# Smartfin_Main_PCBA_Control.net
KiCad netlist of a schematic drawn in Altium Designer
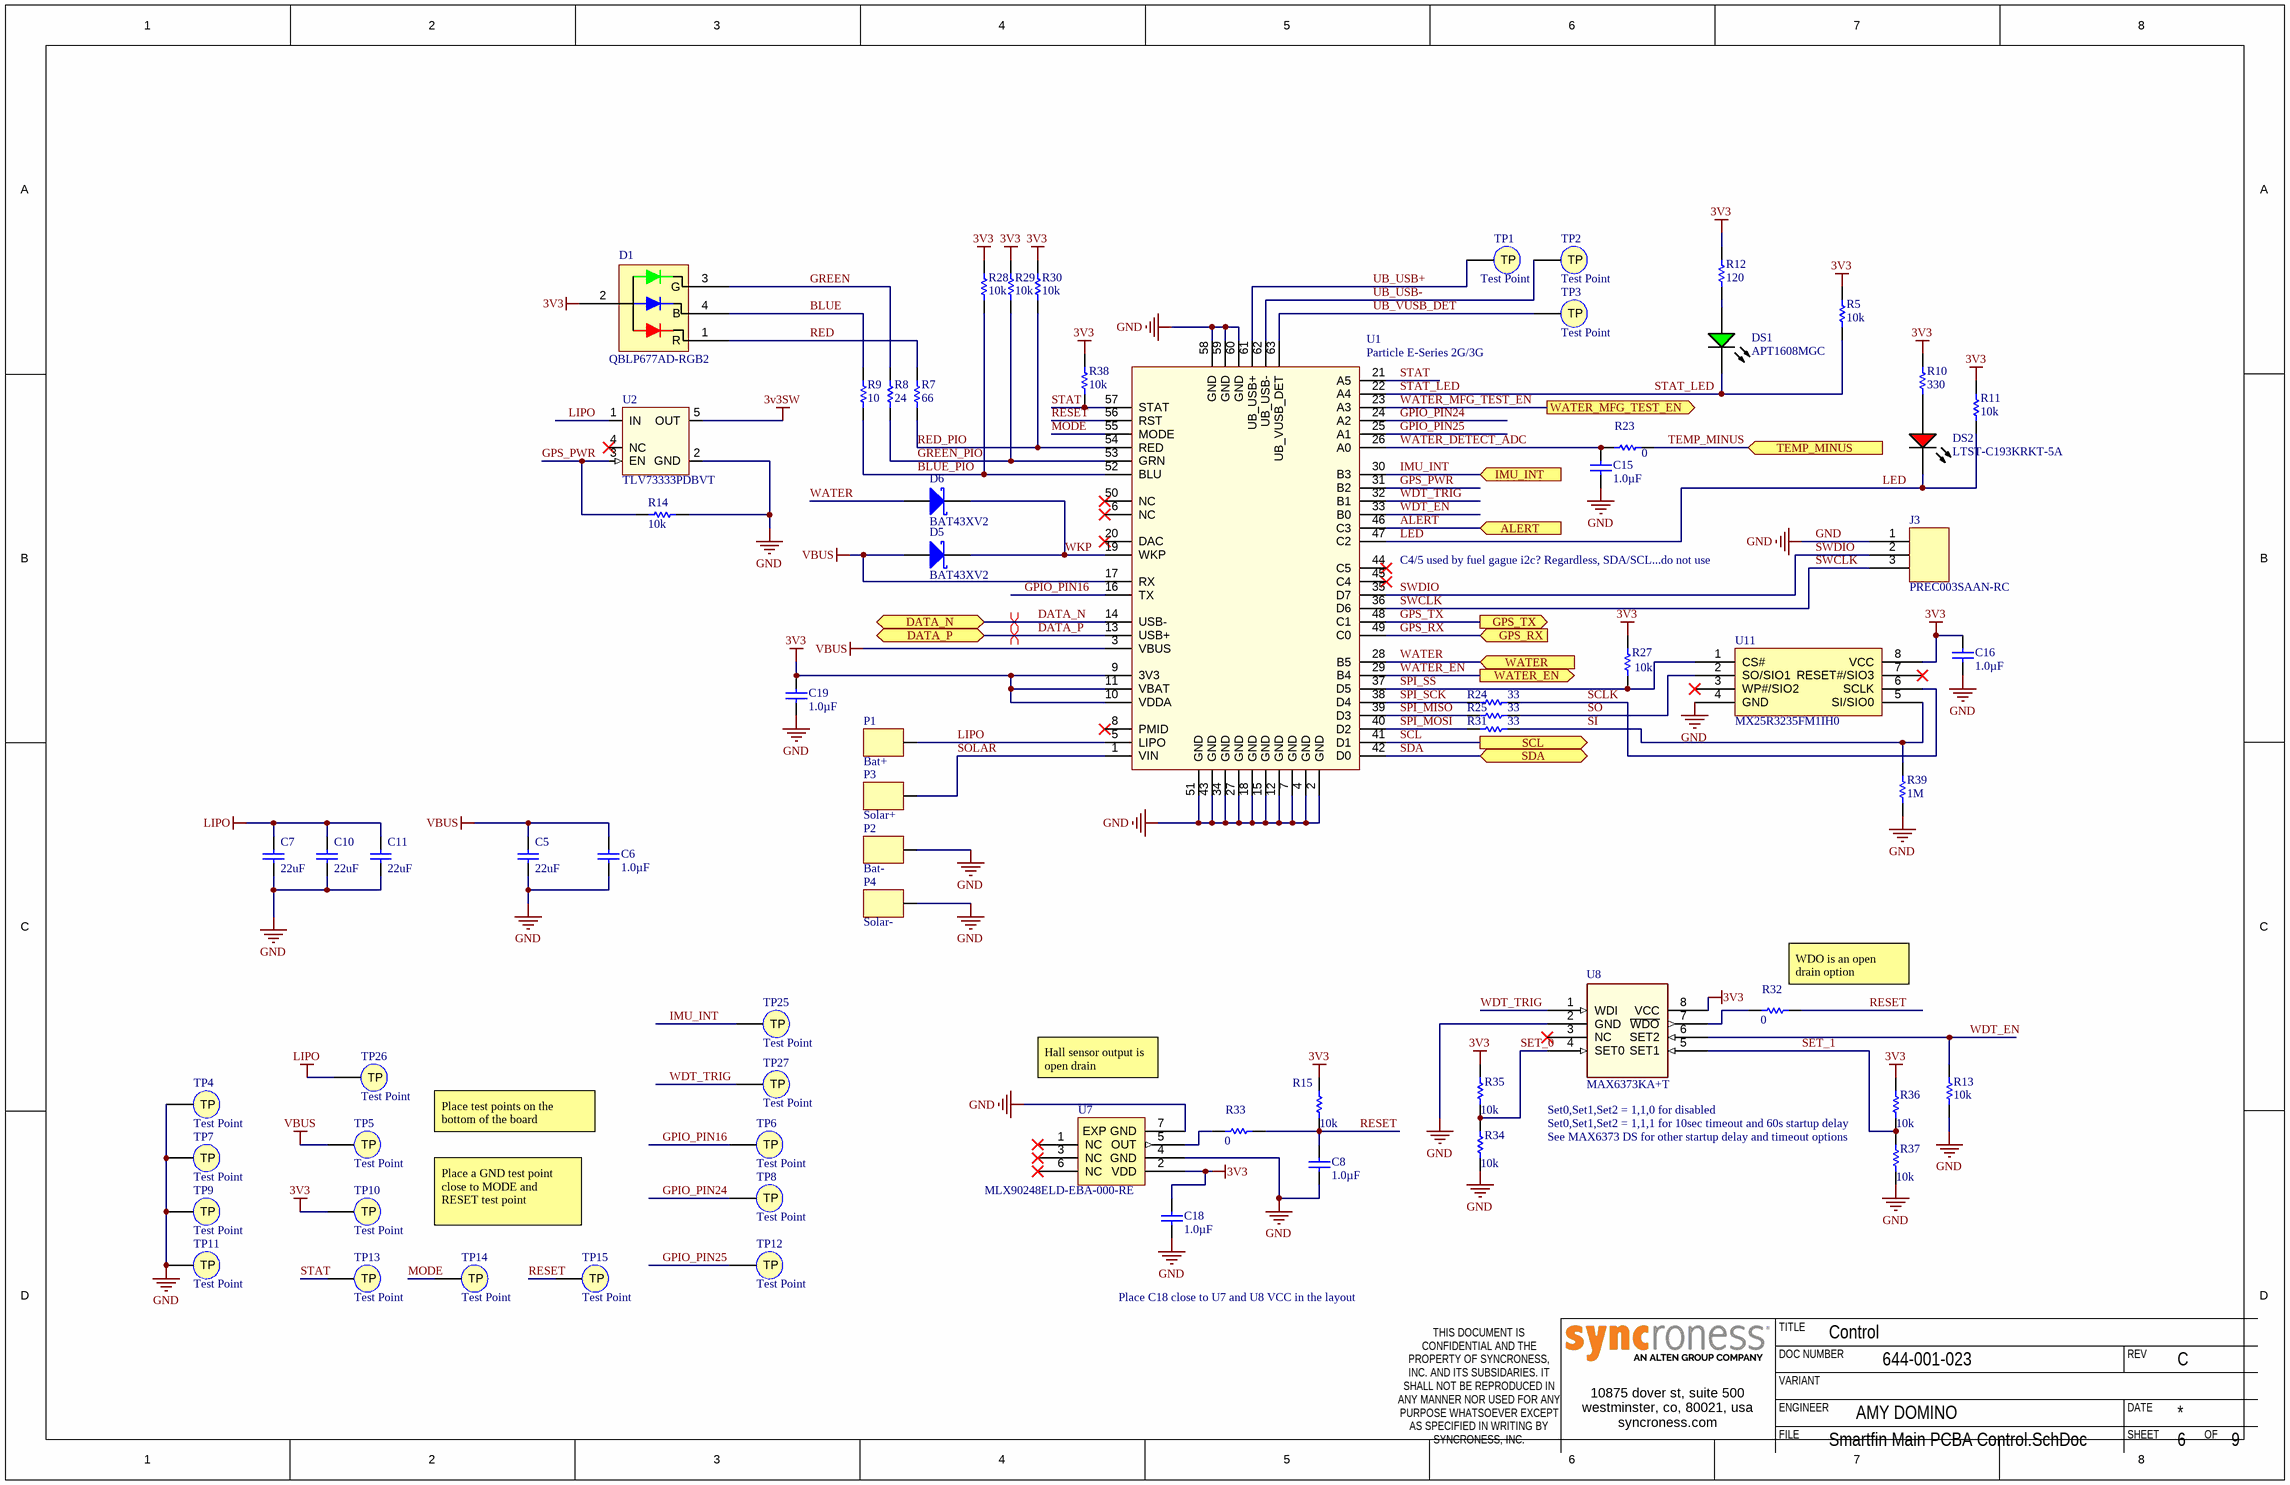
[diagram p0: Smartfin Main PCBA Control.SchDoc]

(export (version "E")
  (design (tool "Eeschema 10.0.6"))
  (components
    (comp (ref "C5")
      (value "22uF")
      (footprint "CAPC0603(1608)100_N")
      (description "CAP CER 22UF 10V X5R 0603")
      (fields (field (name "TOLERANCE") "20%") (field (name "MANUFACTURER") "Murata Electronics"))
      (libsource (lib "Syncroness Vault") (part "CAP"))
    )
    (comp (ref "C6")
      (value "1.0µF")
      (footprint "CAPC0402(1005)60_N")
      (description "CAP CER 1UF 10V 10% X5R 0402")
      (fields
        (field (name "MANUFACTURER") "Yageo")
        (field (name "MANUFACTURER PART NUMBER") "CC0402KRX5R6BB105")
      )
      (libsource (lib "Syncroness Vault") (part "CAP"))
    )
    (comp (ref "C7")
      (value "22uF")
      (footprint "CAPC0603(1608)100_N")
      (description "CAP CER 22UF 10V X5R 0603")
      (fields (field (name "TOLERANCE") "20%") (field (name "MANUFACTURER") "Murata Electronics"))
      (libsource (lib "Syncroness Vault") (part "CAP"))
    )
    (comp (ref "C8")
      (value "1.0µF")
      (footprint "CAPC0402(1005)60_N")
      (description "CAP CER 1UF 10V 10% X5R 0402")
      (fields
        (field (name "MANUFACTURER") "Yageo")
        (field (name "MANUFACTURER PART NUMBER") "CC0402KRX5R6BB105")
      )
      (libsource (lib "Syncroness Vault") (part "CAP"))
    )
    (comp (ref "C10")
      (value "22uF")
      (footprint "CAPC0603(1608)100_N")
      (description "CAP CER 22UF 10V X5R 0603")
      (fields (field (name "TOLERANCE") "20%") (field (name "MANUFACTURER") "Murata Electronics"))
      (libsource (lib "Syncroness Vault") (part "CAP"))
    )
    (comp (ref "C11")
      (value "22uF")
      (footprint "CAPC0603(1608)100_N")
      (description "CAP CER 22UF 10V X5R 0603")
      (fields (field (name "TOLERANCE") "20%") (field (name "MANUFACTURER") "Murata Electronics"))
      (libsource (lib "Syncroness Vault") (part "CAP"))
    )
    (comp (ref "C15")
      (value "1.0µF")
      (footprint "CAPC0402(1005)60_N")
      (description "CAP CER 1UF 10V 10% X5R 0402")
      (fields
        (field (name "MANUFACTURER") "Yageo")
        (field (name "MANUFACTURER PART NUMBER") "CC0402KRX5R6BB105")
      )
      (libsource (lib "Syncroness Vault") (part "CAP"))
    )
    (comp (ref "C16")
      (value "1.0µF")
      (footprint "CAPC0402(1005)60_N")
      (description "CAP CER 1UF 10V 10% X5R 0402")
      (fields
        (field (name "MANUFACTURER") "Yageo")
        (field (name "MANUFACTURER PART NUMBER") "CC0402KRX5R6BB105")
      )
      (libsource (lib "Syncroness Vault") (part "CAP"))
    )
    (comp (ref "C18")
      (value "1.0µF")
      (footprint "CAPC0402(1005)60_N")
      (description "CAP CER 1UF 10V 10% X5R 0402")
      (fields
        (field (name "MANUFACTURER") "Yageo")
        (field (name "MANUFACTURER PART NUMBER") "CC0402KRX5R6BB105")
      )
      (libsource (lib "Syncroness Vault") (part "CAP"))
    )
    (comp (ref "C19")
      (value "1.0µF")
      (footprint "CAPC0402(1005)60_N")
      (description "CAP CER 1UF 10V 10% X5R 0402")
      (fields
        (field (name "MANUFACTURER") "Yageo")
        (field (name "MANUFACTURER PART NUMBER") "CC0402KRX5R6BB105")
      )
      (libsource (lib "Syncroness Vault") (part "CAP"))
    )
    (comp (ref "D1")
      (value "QBLP677AD-RGB2")
      (footprint "QBLP677AD-RGB2-Footprint-1")
      (description "LED RGB, 3528 PLCC4 DOME LENS, 2")
      (fields (field (name "MANUFACTURER") "QT Brightek (QTB)"))
      (libsource (lib "Syncroness Vault") (part "QBLP677-RGB(HIGHBRIGHT)"))
    )
    (comp (ref "D5")
      (value "BAT43XV2")
      (footprint "SOD-523F")
      (description "DIODE SCHOTTKY 30V 200MA SOD523F")
      (fields (field (name "MANUFACTURER") "ON Semiconductor"))
      (libsource (lib "Syncroness Vault") (part "Schottky Diode"))
    )
    (comp (ref "D6")
      (value "BAT43XV2")
      (footprint "SOD-523F")
      (description "DIODE SCHOTTKY 30V 200MA SOD523F")
      (fields (field (name "MANUFACTURER") "ON Semiconductor"))
      (libsource (lib "Syncroness Vault") (part "Schottky Diode"))
    )
    (comp (ref "DS1")
      (value "APT1608MGC")
      (footprint "LED1608X08N")
      (description "LED 1.6X0.8MM 570NM GRN CLR SMD")
      (fields (field (name "MANUFACTURER") "Kingbright"))
      (libsource (lib "Syncroness Vault") (part "Green LED"))
    )
    (comp (ref "DS2")
      (value "LTST-C193KRKT-5A")
      (footprint "LTST-C193KRKT-5A_V")
      (description "LED RED CLEAR CHIP SMD 0603")
      (fields (field (name "MANUFACTURER") "Lite-On Inc."))
      (libsource (lib "Syncroness Vault") (part "LED-RED-AK-2"))
    )
    (comp (ref "J3")
      (value "PREC003SAAN-RC")
      (footprint "HDR_Single_100mil_3D_3")
      (description "CONN HEADER .100\" SNGL STR 3POS")
      (fields (field (name "MANUFACTURER") "Sullins Connector Solutions"))
      (libsource (lib "Syncroness Vault") (part "PREC003SAAN-RC"))
    )
    (comp (ref "P1")
      (value "Bat+")
      (footprint "Battery Pad-Footprint-1")
      (description "Battery Pad for Smartfin Main board")
      (libsource (lib "Syncroness Vault") (part "Battery Pad"))
    )
    (comp (ref "P2")
      (value "Bat-")
      (footprint "Battery Pad-Footprint-1")
      (description "Battery Pad for Smartfin Main board")
      (libsource (lib "Syncroness Vault") (part "Battery Pad"))
    )
    (comp (ref "P3")
      (value "Solar+")
      (footprint "Battery Pad-Footprint-1")
      (description "Battery Pad for Smartfin Main board")
      (libsource (lib "Syncroness Vault") (part "Battery Pad"))
    )
    (comp (ref "P4")
      (value "Solar-")
      (footprint "Battery Pad-Footprint-1")
      (description "Battery Pad for Smartfin Main board")
      (libsource (lib "Syncroness Vault") (part "Battery Pad"))
    )
    (comp (ref "R5")
      (value "10k")
      (footprint "RESC0402(1005)_N")
      (description "RES SMD 10K OHM 0.1% 1/16W 0402")
      (fields
        (field (name "TOLERANCE") "±0.1%")
        (field (name "MANUFACTURER") "Panasonic Electronic Components")
      )
      (libsource (lib "Syncroness Vault") (part "RES"))
    )
    (comp (ref "R7")
      (value "66")
      (footprint "RESC1005X40X25LL05T10")
      (description "Res Thick Film 0402 66.5 Ohm 1% 1/16W ±100ppm/°C Molded SMD Paper T/R")
      (fields (field (name "PART NUMBER") "RC0402FR-0766R5L") (field (name "MANUFACTURER") "Yageo"))
      (libsource (lib "Altium Content Vault") (part "RES"))
    )
    (comp (ref "R8")
      (value "24")
      (footprint "RESC1005X40X25ML10T10")
      (fields
        (field (name "MANUFACTURER") "TE Connectivity / AMP")
        (field (name "PART NUMBER") "CRG0402F24R")
        (field (name "TOLERANCE") "1%")
      )
      (libsource (lib "Altium Content Vault") (part "RES"))
    )
    (comp (ref "R9")
      (value "10")
      (footprint "RESC1005X40X25ML05T10")
      (fields
        (field (name "MANUFACTURER") "Yageo / Phycomp")
        (field (name "PART NUMBER") "RC0402FR-0710RL")
        (field (name "TOLERANCE") "1%")
      )
      (libsource (lib "Altium Content Vault") (part "RES"))
    )
    (comp (ref "R10")
      (value "330")
      (footprint "RESC1005X04N")
      (description "RES SMD 330 OHM 1% 1/16W 0402")
      (fields
        (field (name "MANUFACTURER") "Vishay Dale")
        (field (name "MANUFACTURER PART NUMBER") "CRCW0402330RFKED")
      )
      (libsource (lib "Syncroness Vault") (part "RES"))
    )
    (comp (ref "R11")
      (value "10k")
      (footprint "RESC0402(1005)_N")
      (description "RES SMD 10K OHM 0.1% 1/16W 0402")
      (fields
        (field (name "TOLERANCE") "±0.1%")
        (field (name "MANUFACTURER") "Panasonic Electronic Components")
      )
      (libsource (lib "Syncroness Vault") (part "RES"))
    )
    (comp (ref "R12")
      (value "120")
      (footprint "RESC1005X04N")
      (description "RES SMD 120 OHM 5% 1/16W 0402")
      (fields
        (field (name "MANUFACTURER") "Vishay Dale")
        (field (name "MANUFACTURER PART NUMBER") "CRCW0402120RJNED")
      )
      (libsource (lib "Syncroness Vault") (part "RES"))
    )
    (comp (ref "R13")
      (value "10k")
      (footprint "RESC0402(1005)_N")
      (description "RES SMD 10K OHM 0.1% 1/16W 0402")
      (fields
        (field (name "TOLERANCE") "±0.1%")
        (field (name "MANUFACTURER") "Panasonic Electronic Components")
      )
      (libsource (lib "Syncroness Vault") (part "RES"))
    )
    (comp (ref "R14")
      (value "10k")
      (footprint "RESC0402(1005)_N")
      (description "RES SMD 10K OHM 0.1% 1/16W 0402")
      (fields
        (field (name "TOLERANCE") "±0.1%")
        (field (name "MANUFACTURER") "Panasonic Electronic Components")
      )
      (libsource (lib "Syncroness Vault") (part "RES"))
    )
    (comp (ref "R15")
      (value "10k")
      (footprint "RESC0402(1005)_N")
      (description "RES SMD 10K OHM 0.1% 1/16W 0402")
      (fields
        (field (name "TOLERANCE") "±0.1%")
        (field (name "MANUFACTURER") "Panasonic Electronic Components")
      )
      (libsource (lib "Syncroness Vault") (part "RES"))
    )
    (comp (ref "R23")
      (value "0")
      (footprint "RESC0402(1005)_N")
      (description "RES 0.0 OHM 1/16W 0402 SMD")
      (fields
        (field (name "MANUFACTURER") "Vishay/Dale")
        (field (name "MANUFACTURER PART NUMBER") "CRCW04020000Z0ED")
      )
      (libsource (lib "Syncroness Vault") (part "RES"))
    )
    (comp (ref "R24")
      (value "33")
      (footprint "RESC1005X04N")
      (description "RES SMD 33 OHM 5% 1/16W 0402")
      (fields
        (field (name "MANUFACTURER") "Vishay Dale")
        (field (name "MANUFACTURER PART NUMBER") "CRCW040233R0JNED")
      )
      (libsource (lib "Syncroness Vault") (part "RES"))
    )
    (comp (ref "R25")
      (value "33")
      (footprint "RESC1005X04N")
      (description "RES SMD 33 OHM 5% 1/16W 0402")
      (fields
        (field (name "MANUFACTURER") "Vishay Dale")
        (field (name "MANUFACTURER PART NUMBER") "CRCW040233R0JNED")
      )
      (libsource (lib "Syncroness Vault") (part "RES"))
    )
    (comp (ref "R27")
      (value "10k")
      (footprint "RESC0402(1005)_N")
      (description "RES SMD 10K OHM 0.1% 1/16W 0402")
      (fields
        (field (name "TOLERANCE") "±0.1%")
        (field (name "MANUFACTURER") "Panasonic Electronic Components")
      )
      (libsource (lib "Syncroness Vault") (part "RES"))
    )
    (comp (ref "R28")
      (value "10k")
      (footprint "RESC0402(1005)_N")
      (description "RES SMD 10K OHM 0.1% 1/16W 0402")
      (fields
        (field (name "TOLERANCE") "±0.1%")
        (field (name "MANUFACTURER") "Panasonic Electronic Components")
      )
      (libsource (lib "Syncroness Vault") (part "RES"))
    )
    (comp (ref "R29")
      (value "10k")
      (footprint "RESC0402(1005)_N")
      (description "RES SMD 10K OHM 0.1% 1/16W 0402")
      (fields
        (field (name "TOLERANCE") "±0.1%")
        (field (name "MANUFACTURER") "Panasonic Electronic Components")
      )
      (libsource (lib "Syncroness Vault") (part "RES"))
    )
    (comp (ref "R30")
      (value "10k")
      (footprint "RESC0402(1005)_N")
      (description "RES SMD 10K OHM 0.1% 1/16W 0402")
      (fields
        (field (name "TOLERANCE") "±0.1%")
        (field (name "MANUFACTURER") "Panasonic Electronic Components")
      )
      (libsource (lib "Syncroness Vault") (part "RES"))
    )
    (comp (ref "R31")
      (value "33")
      (footprint "RESC1005X04N")
      (description "RES SMD 33 OHM 5% 1/16W 0402")
      (fields
        (field (name "MANUFACTURER") "Vishay Dale")
        (field (name "MANUFACTURER PART NUMBER") "CRCW040233R0JNED")
      )
      (libsource (lib "Syncroness Vault") (part "RES"))
    )
    (comp (ref "R32")
      (value "0")
      (footprint "RESC0402(1005)_N")
      (description "RES 0.0 OHM 1/16W 0402 SMD")
      (fields
        (field (name "MANUFACTURER") "Vishay/Dale")
        (field (name "MANUFACTURER PART NUMBER") "CRCW04020000Z0ED")
      )
      (libsource (lib "Syncroness Vault") (part "RES"))
    )
    (comp (ref "R33")
      (value "0")
      (footprint "RESC0402(1005)_N")
      (description "RES 0.0 OHM 1/16W 0402 SMD")
      (fields
        (field (name "MANUFACTURER") "Vishay/Dale")
        (field (name "MANUFACTURER PART NUMBER") "CRCW04020000Z0ED")
      )
      (libsource (lib "Syncroness Vault") (part "RES"))
    )
    (comp (ref "R34")
      (value "10k")
      (footprint "RESC0402(1005)_N")
      (description "RES SMD 10K OHM 0.1% 1/16W 0402")
      (fields
        (field (name "TOLERANCE") "±0.1%")
        (field (name "MANUFACTURER") "Panasonic Electronic Components")
      )
      (libsource (lib "Syncroness Vault") (part "RES"))
    )
    (comp (ref "R35")
      (value "10k")
      (footprint "RESC0402(1005)_N")
      (description "RES SMD 10K OHM 0.1% 1/16W 0402")
      (fields
        (field (name "TOLERANCE") "±0.1%")
        (field (name "MANUFACTURER") "Panasonic Electronic Components")
      )
      (libsource (lib "Syncroness Vault") (part "RES"))
    )
    (comp (ref "R36")
      (value "10k")
      (footprint "RESC0402(1005)_N")
      (description "RES SMD 10K OHM 0.1% 1/16W 0402")
      (fields
        (field (name "TOLERANCE") "±0.1%")
        (field (name "MANUFACTURER") "Panasonic Electronic Components")
      )
      (libsource (lib "Syncroness Vault") (part "RES"))
    )
    (comp (ref "R37")
      (value "10k")
      (footprint "RESC0402(1005)_N")
      (description "RES SMD 10K OHM 0.1% 1/16W 0402")
      (fields
        (field (name "TOLERANCE") "±0.1%")
        (field (name "MANUFACTURER") "Panasonic Electronic Components")
      )
      (libsource (lib "Syncroness Vault") (part "RES"))
    )
    (comp (ref "R38")
      (value "10k")
      (footprint "RESC0402(1005)_N")
      (description "RES SMD 10K OHM 0.1% 1/16W 0402")
      (fields
        (field (name "TOLERANCE") "±0.1%")
        (field (name "MANUFACTURER") "Panasonic Electronic Components")
      )
      (libsource (lib "Syncroness Vault") (part "RES"))
    )
    (comp (ref "R39")
      (value "1M")
      (footprint "RESC0402(1005)_N")
      (description "RES 1.0M OHM 1/16W 5% 0402 SMD")
      (fields (field (name "MANUFACTURER PART NUMBER") "RC0402JR-071ML") (field (name "TOLERANCE") "5%"))
      (libsource (lib "Syncroness Vault") (part "RES"))
    )
    (comp (ref "TP1")
      (value "Test Point")
      (footprint "TESTPAD_ICT")
      (description "ICT Test Point")
      (libsource (lib "Syncroness Vault") (part "TestPointPadOnly"))
    )
    (comp (ref "TP2")
      (value "Test Point")
      (footprint "TESTPAD_ICT")
      (description "ICT Test Point")
      (libsource (lib "Syncroness Vault") (part "TestPointPadOnly"))
    )
    (comp (ref "TP3")
      (value "Test Point")
      (footprint "TESTPAD_ICT")
      (description "ICT Test Point")
      (libsource (lib "Syncroness Vault") (part "TestPointPadOnly"))
    )
    (comp (ref "TP4")
      (value "Test Point")
      (footprint "TESTPAD_ICT")
      (description "ICT Test Point")
      (libsource (lib "Syncroness Vault") (part "TestPointPadOnly"))
    )
    (comp (ref "TP5")
      (value "Test Point")
      (footprint "TESTPAD_ICT")
      (description "ICT Test Point")
      (libsource (lib "Syncroness Vault") (part "TestPointPadOnly"))
    )
    (comp (ref "TP6")
      (value "Test Point")
      (footprint "TESTPAD_ICT")
      (description "ICT Test Point")
      (libsource (lib "Syncroness Vault") (part "TestPointPadOnly"))
    )
    (comp (ref "TP7")
      (value "Test Point")
      (footprint "TESTPAD_ICT")
      (description "ICT Test Point")
      (libsource (lib "Syncroness Vault") (part "TestPointPadOnly"))
    )
    (comp (ref "TP8")
      (value "Test Point")
      (footprint "TESTPAD_ICT")
      (description "ICT Test Point")
      (libsource (lib "Syncroness Vault") (part "TestPointPadOnly"))
    )
    (comp (ref "TP9")
      (value "Test Point")
      (footprint "TESTPAD_ICT")
      (description "ICT Test Point")
      (libsource (lib "Syncroness Vault") (part "TestPointPadOnly"))
    )
    (comp (ref "TP10")
      (value "Test Point")
      (footprint "TESTPAD_ICT")
      (description "ICT Test Point")
      (libsource (lib "Syncroness Vault") (part "TestPointPadOnly"))
    )
    (comp (ref "TP11")
      (value "Test Point")
      (footprint "TESTPAD_ICT")
      (description "ICT Test Point")
      (libsource (lib "Syncroness Vault") (part "TestPointPadOnly"))
    )
    (comp (ref "TP12")
      (value "Test Point")
      (footprint "TESTPAD_ICT")
      (description "ICT Test Point")
      (libsource (lib "Syncroness Vault") (part "TestPointPadOnly"))
    )
    (comp (ref "TP13")
      (value "Test Point")
      (footprint "TESTPAD_ICT")
      (description "ICT Test Point")
      (libsource (lib "Syncroness Vault") (part "TestPointPadOnly"))
    )
    (comp (ref "TP14")
      (value "Test Point")
      (footprint "TESTPAD_ICT")
      (description "ICT Test Point")
      (libsource (lib "Syncroness Vault") (part "TestPointPadOnly"))
    )
    (comp (ref "TP15")
      (value "Test Point")
      (footprint "TESTPAD_ICT")
      (description "ICT Test Point")
      (libsource (lib "Syncroness Vault") (part "TestPointPadOnly"))
    )
    (comp (ref "TP25")
      (value "Test Point")
      (footprint "TESTPAD_ICT")
      (description "ICT Test Point")
      (libsource (lib "Syncroness Vault") (part "TestPointPadOnly"))
    )
    (comp (ref "TP26")
      (value "Test Point")
      (footprint "TESTPAD_ICT")
      (description "ICT Test Point")
      (libsource (lib "Syncroness Vault") (part "TestPointPadOnly"))
    )
    (comp (ref "TP27")
      (value "Test Point")
      (footprint "TESTPAD_ICT")
      (description "ICT Test Point")
      (libsource (lib "Syncroness Vault") (part "TestPointPadOnly"))
    )
    (comp (ref "U1")
      (value "Particle E-Series 2G/3G")
      (footprint "Particle E-Series-Footprint-1")
      (description "Global 2G/3G, U-blox SARA-U201 Modem")
      (fields (field (name "MANUFACTURER") "Particle") (field (name "MANUFACTURER PART NUMBER") "E310"))
      (libsource (lib "Syncroness Vault") (part "Particle E-Series, Global 2G/3G"))
    )
    (comp (ref "U2")
      (value "TLV73333PDBVT")
      (footprint "TLV73333PDBVR-Footprint-1")
      (description "IC REG LINEAR 3.3V 300MA SOT23-5")
      (fields (field (name "MANUFACTURER") "Texas Instruments"))
      (libsource (lib "Syncroness Vault") (part "TLV73333PDBVR"))
    )
    (comp (ref "U7")
      (value "MLX90248ELD-EBA-000-RE")
      (footprint "MLX90248ELD-EBA-000-RE-Footprint-1")
      (description "MAGNETIC SWITCH OMNIPOLAR 6UTQFN")
      (fields (field (name "MANUFACTURER") "Melexis"))
      (libsource (lib "Syncroness Vault") (part "MLX90248ELD-EBA-000-RE"))
    )
    (comp (ref "U8")
      (value "MAX6373KA+T")
      (footprint "MAX6373KA+T-Footprint-1")
      (description "IC WATCHDOG TIMER SOT23-8")
      (fields (field (name "MANUFACTURER") "Maxim Integrated"))
      (libsource (lib "Syncroness Vault") (part "MAX6373KA+T"))
    )
    (comp (ref "U11")
      (value "MX25R3235FM1IH0")
      (footprint "SOP127P600X175-8N")
      (description "IC FLASH 32M SPI 80MHZ 8SOP")
      (fields (field (name "MANUFACTURER") "Macronix"))
      (libsource (lib "Syncroness Vault") (part "MX25R3235FM1IH0"))
    )
  )
  (nets
    (net (code "1") (name "/ALERT") (class "Default")
      (node (ref "U1") (pin "46") (pinfunction "C3_46") (pintype "passive"))
    )
    (net (code "2") (name "/BLUE") (class "Default")
      (node (ref "D1") (pin "4") (pinfunction "B_4") (pintype "passive"))
      (node (ref "R9") (pin "2") (pinfunction "2_2") (pintype "passive"))
    )
    (net (code "3") (name "/BLUE_PIO") (class "Default")
      (node (ref "R28") (pin "1") (pinfunction "1_1") (pintype "passive"))
      (node (ref "R9") (pin "1") (pinfunction "1_1") (pintype "passive"))
      (node (ref "U1") (pin "52") (pinfunction "BLU_52") (pintype "passive"))
    )
    (net (code "4") (name "/DATA_N") (class "Default")
      (node (ref "U1") (pin "14") (pinfunction "USB-_14") (pintype "passive"))
    )
    (net (code "5") (name "/DATA_P") (class "Default")
      (node (ref "U1") (pin "13") (pinfunction "USB+_13") (pintype "passive"))
    )
    (net (code "6") (name "/GPIO_PIN16") (class "Default")
      (node (ref "TP6") (pin "1") (pinfunction "TP_1") (pintype "passive"))
      (node (ref "U1") (pin "16") (pinfunction "TX_16") (pintype "passive"))
    )
    (net (code "7") (name "/GPIO_PIN24") (class "Default")
      (node (ref "TP8") (pin "1") (pinfunction "TP_1") (pintype "passive"))
      (node (ref "U1") (pin "24") (pinfunction "A2_24") (pintype "passive"))
    )
    (net (code "8") (name "/GPIO_PIN25") (class "Default")
      (node (ref "TP12") (pin "1") (pinfunction "TP_1") (pintype "passive"))
      (node (ref "U1") (pin "25") (pinfunction "A1_25") (pintype "passive"))
    )
    (net (code "9") (name "/GPS_PWR") (class "Default")
      (node (ref "R14") (pin "2") (pinfunction "2_2") (pintype "passive"))
      (node (ref "U1") (pin "31") (pinfunction "B2_31") (pintype "passive"))
      (node (ref "U2") (pin "3") (pinfunction "EN_3") (pintype "input"))
    )
    (net (code "10") (name "/GPS_RX") (class "Default")
      (node (ref "U1") (pin "49") (pinfunction "C0_49") (pintype "passive"))
    )
    (net (code "11") (name "/GPS_TX") (class "Default")
      (node (ref "U1") (pin "48") (pinfunction "C1_48") (pintype "passive"))
    )
    (net (code "12") (name "/GREEN") (class "Default")
      (node (ref "D1") (pin "3") (pinfunction "G_3") (pintype "passive"))
      (node (ref "R8") (pin "2") (pinfunction "2_2") (pintype "passive"))
    )
    (net (code "13") (name "/GREEN_PIO") (class "Default")
      (node (ref "R29") (pin "1") (pinfunction "1_1") (pintype "passive"))
      (node (ref "R8") (pin "1") (pinfunction "1_1") (pintype "passive"))
      (node (ref "U1") (pin "53") (pinfunction "GRN_53") (pintype "passive"))
    )
    (net (code "14") (name "/IMU_INT") (class "Default")
      (node (ref "TP25") (pin "1") (pinfunction "TP_1") (pintype "passive"))
      (node (ref "U1") (pin "30") (pinfunction "B3_30") (pintype "passive"))
    )
    (net (code "15") (name "/LED") (class "Default")
      (node (ref "DS2") (pin "2") (pinfunction "K_2") (pintype "passive"))
      (node (ref "R11") (pin "1") (pinfunction "1_1") (pintype "passive"))
      (node (ref "U1") (pin "47") (pinfunction "C2_47") (pintype "passive"))
    )
    (net (code "16") (name "/MODE") (class "Default")
      (node (ref "TP14") (pin "1") (pinfunction "TP_1") (pintype "passive"))
      (node (ref "U1") (pin "55") (pinfunction "MODE_55") (pintype "passive"))
    )
    (net (code "17") (name "/RED") (class "Default")
      (node (ref "D1") (pin "1") (pinfunction "R_1") (pintype "passive"))
      (node (ref "R7") (pin "2") (pinfunction "2_2") (pintype "passive"))
    )
    (net (code "18") (name "/RED_PIO") (class "Default")
      (node (ref "R30") (pin "1") (pinfunction "1_1") (pintype "passive"))
      (node (ref "R7") (pin "1") (pinfunction "1_1") (pintype "passive"))
      (node (ref "U1") (pin "54") (pinfunction "RED_54") (pintype "passive"))
    )
    (net (code "19") (name "/RESET") (class "Default")
      (node (ref "C8") (pin "2") (pinfunction "2_2") (pintype "passive"))
      (node (ref "R15") (pin "1") (pinfunction "1_1") (pintype "passive"))
      (node (ref "R32") (pin "2") (pinfunction "2_2") (pintype "passive"))
      (node (ref "R33") (pin "2") (pinfunction "2_2") (pintype "passive"))
      (node (ref "TP15") (pin "1") (pinfunction "TP_1") (pintype "passive"))
      (node (ref "U1") (pin "56") (pinfunction "RST_56") (pintype "passive"))
    )
    (net (code "20") (name "/SCL") (class "Default")
      (node (ref "U1") (pin "41") (pinfunction "D1_41") (pintype "passive"))
    )
    (net (code "21") (name "/SCLK") (class "Default")
      (node (ref "R24") (pin "2") (pinfunction "2_2") (pintype "passive"))
      (node (ref "U11") (pin "6") (pinfunction "SCLK_6") (pintype "passive"))
    )
    (net (code "22") (name "/SDA") (class "Default")
      (node (ref "U1") (pin "42") (pinfunction "D0_42") (pintype "passive"))
    )
    (net (code "23") (name "/SET_0") (class "Default")
      (node (ref "R34") (pin "2") (pinfunction "2_2") (pintype "passive"))
      (node (ref "R35") (pin "1") (pinfunction "1_1") (pintype "passive"))
      (node (ref "U8") (pin "4") (pinfunction "SET0_4") (pintype "input"))
    )
    (net (code "24") (name "/SET_1") (class "Default")
      (node (ref "R36") (pin "1") (pinfunction "1_1") (pintype "passive"))
      (node (ref "R37") (pin "2") (pinfunction "2_2") (pintype "passive"))
      (node (ref "U8") (pin "5") (pinfunction "SET1_5") (pintype "input"))
    )
    (net (code "25") (name "/SI") (class "Default")
      (node (ref "R31") (pin "2") (pinfunction "2_2") (pintype "passive"))
      (node (ref "R39") (pin "2") (pinfunction "2_2") (pintype "passive"))
      (node (ref "U11") (pin "5") (pinfunction "SI/SIO0_5") (pintype "passive"))
    )
    (net (code "26") (name "/SO") (class "Default")
      (node (ref "R25") (pin "2") (pinfunction "2_2") (pintype "passive"))
      (node (ref "U11") (pin "2") (pinfunction "SO/SIO1_2") (pintype "passive"))
    )
    (net (code "27") (name "/SOLAR") (class "Default")
      (node (ref "P3") (pin "1") (pinfunction "1_1") (pintype "passive"))
      (node (ref "U1") (pin "1") (pinfunction "VIN_1") (pintype "passive"))
    )
    (net (code "28") (name "/SPI_MISO") (class "Default")
      (node (ref "R25") (pin "1") (pinfunction "1_1") (pintype "passive"))
      (node (ref "U1") (pin "39") (pinfunction "D3_39") (pintype "passive"))
    )
    (net (code "29") (name "/SPI_MOSI") (class "Default")
      (node (ref "R31") (pin "1") (pinfunction "1_1") (pintype "passive"))
      (node (ref "U1") (pin "40") (pinfunction "D2_40") (pintype "passive"))
    )
    (net (code "30") (name "/SPI_SCK") (class "Default")
      (node (ref "R24") (pin "1") (pinfunction "1_1") (pintype "passive"))
      (node (ref "U1") (pin "38") (pinfunction "D4_38") (pintype "passive"))
    )
    (net (code "31") (name "/SPI_SS") (class "Default")
      (node (ref "R27") (pin "1") (pinfunction "1_1") (pintype "passive"))
      (node (ref "U1") (pin "37") (pinfunction "D5_37") (pintype "passive"))
      (node (ref "U11") (pin "1") (pinfunction "CS#_1") (pintype "passive"))
    )
    (net (code "32") (name "/STAT") (class "Default")
      (node (ref "R38") (pin "1") (pinfunction "1_1") (pintype "passive"))
      (node (ref "TP13") (pin "1") (pinfunction "TP_1") (pintype "passive"))
      (node (ref "U1") (pin "21") (pinfunction "A5_21") (pintype "passive"))
      (node (ref "U1") (pin "57") (pinfunction "STAT_57") (pintype "passive"))
    )
    (net (code "33") (name "/STAT_LED") (class "Default")
      (node (ref "DS1") (pin "K") (pinfunction "K_K") (pintype "passive"))
      (node (ref "R5") (pin "1") (pinfunction "1_1") (pintype "passive"))
      (node (ref "U1") (pin "22") (pinfunction "A4_22") (pintype "passive"))
    )
    (net (code "34") (name "/SWCLK") (class "Default")
      (node (ref "J3") (pin "3") (pinfunction "3_3") (pintype "passive"))
      (node (ref "U1") (pin "36") (pinfunction "D6_36") (pintype "passive"))
    )
    (net (code "35") (name "/SWDIO") (class "Default")
      (node (ref "J3") (pin "2") (pinfunction "2_2") (pintype "passive"))
      (node (ref "U1") (pin "35") (pinfunction "D7_35") (pintype "passive"))
    )
    (net (code "36") (name "/TEMP_MINUS") (class "Default")
      (node (ref "R23") (pin "2") (pinfunction "2_2") (pintype "passive"))
    )
    (net (code "37") (name "/UB_USB+") (class "Default")
      (node (ref "TP1") (pin "1") (pinfunction "TP_1") (pintype "passive"))
      (node (ref "U1") (pin "61") (pinfunction "UB_USB+_61") (pintype "passive"))
    )
    (net (code "38") (name "/UB_USB-") (class "Default")
      (node (ref "TP2") (pin "1") (pinfunction "TP_1") (pintype "passive"))
      (node (ref "U1") (pin "62") (pinfunction "UB_USB-_62") (pintype "passive"))
    )
    (net (code "39") (name "/UB_VUSB_DET") (class "Default")
      (node (ref "TP3") (pin "1") (pinfunction "TP_1") (pintype "passive"))
      (node (ref "U1") (pin "63") (pinfunction "UB_VUSB_DET_63") (pintype "passive"))
    )
    (net (code "40") (name "/WATER") (class "Default")
      (node (ref "D6") (pin "A") (pinfunction "A_A") (pintype "passive"))
      (node (ref "U1") (pin "28") (pinfunction "B5_28") (pintype "passive"))
    )
    (net (code "41") (name "/WATER_DETECT_ADC") (class "Default")
      (node (ref "C15") (pin "2") (pinfunction "2_2") (pintype "passive"))
      (node (ref "R23") (pin "1") (pinfunction "1_1") (pintype "passive"))
      (node (ref "U1") (pin "26") (pinfunction "A0_26") (pintype "passive"))
    )
    (net (code "42") (name "/WATER_EN") (class "Default")
      (node (ref "U1") (pin "29") (pinfunction "B4_29") (pintype "passive"))
    )
    (net (code "43") (name "/WATER_MFG_TEST_EN") (class "Default")
      (node (ref "U1") (pin "23") (pinfunction "A3_23") (pintype "passive"))
    )
    (net (code "44") (name "/WDT_EN") (class "Default")
      (node (ref "R13") (pin "2") (pinfunction "2_2") (pintype "passive"))
      (node (ref "U1") (pin "33") (pinfunction "B0_33") (pintype "passive"))
      (node (ref "U8") (pin "6") (pinfunction "SET2_6") (pintype "input"))
    )
    (net (code "45") (name "/WDT_TRIG") (class "Default")
      (node (ref "TP27") (pin "1") (pinfunction "TP_1") (pintype "passive"))
      (node (ref "U1") (pin "32") (pinfunction "B1_32") (pintype "passive"))
      (node (ref "U8") (pin "1") (pinfunction "WDI_1") (pintype "input"))
    )
    (net (code "46") (name "/WKP") (class "Default")
      (node (ref "D5") (pin "K") (pinfunction "K_K") (pintype "passive"))
      (node (ref "D6") (pin "K") (pinfunction "K_K") (pintype "passive"))
      (node (ref "U1") (pin "19") (pinfunction "WKP_19") (pintype "passive"))
    )
    (net (code "47") (name "3V3") (class "Default")
      (node (ref "C16") (pin "2") (pinfunction "2_2") (pintype "passive"))
      (node (ref "C18") (pin "2") (pinfunction "2_2") (pintype "passive"))
      (node (ref "C19") (pin "2") (pinfunction "2_2") (pintype "passive"))
      (node (ref "D1") (pin "2") (pinfunction "A_2") (pintype "passive"))
      (node (ref "R10") (pin "2") (pinfunction "2_2") (pintype "passive"))
      (node (ref "R11") (pin "2") (pinfunction "2_2") (pintype "passive"))
      (node (ref "R12") (pin "2") (pinfunction "2_2") (pintype "passive"))
      (node (ref "R15") (pin "2") (pinfunction "2_2") (pintype "passive"))
      (node (ref "R27") (pin "2") (pinfunction "2_2") (pintype "passive"))
      (node (ref "R28") (pin "2") (pinfunction "2_2") (pintype "passive"))
      (node (ref "R29") (pin "2") (pinfunction "2_2") (pintype "passive"))
      (node (ref "R30") (pin "2") (pinfunction "2_2") (pintype "passive"))
      (node (ref "R35") (pin "2") (pinfunction "2_2") (pintype "passive"))
      (node (ref "R36") (pin "2") (pinfunction "2_2") (pintype "passive"))
      (node (ref "R38") (pin "2") (pinfunction "2_2") (pintype "passive"))
      (node (ref "R5") (pin "2") (pinfunction "2_2") (pintype "passive"))
      (node (ref "TP10") (pin "1") (pinfunction "TP_1") (pintype "passive"))
      (node (ref "U1") (pin "10") (pinfunction "VDDA_10") (pintype "passive"))
      (node (ref "U1") (pin "11") (pinfunction "VBAT_11") (pintype "passive"))
      (node (ref "U1") (pin "9") (pinfunction "3V3_9") (pintype "passive"))
      (node (ref "U11") (pin "8") (pinfunction "VCC_8") (pintype "passive"))
      (node (ref "U7") (pin "2") (pinfunction "VDD_2") (pintype "power_in"))
      (node (ref "U8") (pin "8") (pinfunction "VCC_8") (pintype "power_in"))
    )
    (net (code "48") (name "3v3SW") (class "Default")
      (node (ref "U2") (pin "5") (pinfunction "OUT_5") (pintype "power_in"))
    )
    (net (code "49") (name "GND") (class "Default")
      (node (ref "C10") (pin "1") (pinfunction "1_1") (pintype "passive"))
      (node (ref "C11") (pin "1") (pinfunction "1_1") (pintype "passive"))
      (node (ref "C15") (pin "1") (pinfunction "1_1") (pintype "passive"))
      (node (ref "C16") (pin "1") (pinfunction "1_1") (pintype "passive"))
      (node (ref "C18") (pin "1") (pinfunction "1_1") (pintype "passive"))
      (node (ref "C19") (pin "1") (pinfunction "1_1") (pintype "passive"))
      (node (ref "C5") (pin "1") (pinfunction "1_1") (pintype "passive"))
      (node (ref "C6") (pin "1") (pinfunction "1_1") (pintype "passive"))
      (node (ref "C7") (pin "1") (pinfunction "1_1") (pintype "passive"))
      (node (ref "C8") (pin "1") (pinfunction "1_1") (pintype "passive"))
      (node (ref "J3") (pin "1") (pinfunction "1_1") (pintype "passive"))
      (node (ref "P2") (pin "1") (pinfunction "1_1") (pintype "passive"))
      (node (ref "P4") (pin "1") (pinfunction "1_1") (pintype "passive"))
      (node (ref "R13") (pin "1") (pinfunction "1_1") (pintype "passive"))
      (node (ref "R14") (pin "1") (pinfunction "1_1") (pintype "passive"))
      (node (ref "R34") (pin "1") (pinfunction "1_1") (pintype "passive"))
      (node (ref "R37") (pin "1") (pinfunction "1_1") (pintype "passive"))
      (node (ref "R39") (pin "1") (pinfunction "1_1") (pintype "passive"))
      (node (ref "TP11") (pin "1") (pinfunction "TP_1") (pintype "passive"))
      (node (ref "TP4") (pin "1") (pinfunction "TP_1") (pintype "passive"))
      (node (ref "TP7") (pin "1") (pinfunction "TP_1") (pintype "passive"))
      (node (ref "TP9") (pin "1") (pinfunction "TP_1") (pintype "passive"))
      (node (ref "U1") (pin "12") (pinfunction "GND_12") (pintype "passive"))
      (node (ref "U1") (pin "15") (pinfunction "GND_15") (pintype "passive"))
      (node (ref "U1") (pin "18") (pinfunction "GND_18") (pintype "passive"))
      (node (ref "U1") (pin "2") (pinfunction "GND_2") (pintype "passive"))
      (node (ref "U1") (pin "27") (pinfunction "GND_27") (pintype "passive"))
      (node (ref "U1") (pin "34") (pinfunction "GND_34") (pintype "passive"))
      (node (ref "U1") (pin "4") (pinfunction "GND_4") (pintype "passive"))
      (node (ref "U1") (pin "43") (pinfunction "GND_43") (pintype "passive"))
      (node (ref "U1") (pin "51") (pinfunction "GND_51") (pintype "passive"))
      (node (ref "U1") (pin "58") (pinfunction "GND_58") (pintype "passive"))
      (node (ref "U1") (pin "59") (pinfunction "GND_59") (pintype "passive"))
      (node (ref "U1") (pin "60") (pinfunction "GND_60") (pintype "passive"))
      (node (ref "U1") (pin "7") (pinfunction "GND_7") (pintype "passive"))
      (node (ref "U11") (pin "4") (pinfunction "GND_4") (pintype "passive"))
      (node (ref "U2") (pin "2") (pinfunction "GND_2") (pintype "power_in"))
      (node (ref "U7") (pin "4") (pinfunction "GND_4") (pintype "power_in"))
      (node (ref "U7") (pin "7") (pinfunction "EXP_GND_7") (pintype "power_in"))
      (node (ref "U8") (pin "2") (pinfunction "GND_2") (pintype "power_in"))
    )
    (net (code "50") (name "LIPO") (class "Default")
      (node (ref "C10") (pin "2") (pinfunction "2_2") (pintype "passive"))
      (node (ref "C11") (pin "2") (pinfunction "2_2") (pintype "passive"))
      (node (ref "C7") (pin "2") (pinfunction "2_2") (pintype "passive"))
      (node (ref "P1") (pin "1") (pinfunction "1_1") (pintype "passive"))
      (node (ref "TP26") (pin "1") (pinfunction "TP_1") (pintype "passive"))
      (node (ref "U1") (pin "5") (pinfunction "LIPO_5") (pintype "passive"))
      (node (ref "U2") (pin "1") (pinfunction "IN_1") (pintype "power_in"))
    )
    (net (code "51") (name "Net-(DS1-PadA)") (class "Default")
      (node (ref "DS1") (pin "A") (pinfunction "A_A") (pintype "passive"))
      (node (ref "R12") (pin "1") (pinfunction "1_1") (pintype "passive"))
    )
    (net (code "52") (name "Net-(DS2-A)") (class "Default")
      (node (ref "DS2") (pin "1") (pinfunction "A_1") (pintype "passive"))
      (node (ref "R10") (pin "1") (pinfunction "1_1") (pintype "passive"))
    )
    (net (code "53") (name "Net-(U7-OUT)") (class "Default")
      (node (ref "R33") (pin "1") (pinfunction "1_1") (pintype "passive"))
      (node (ref "U7") (pin "5") (pinfunction "OUT_5") (pintype "output"))
    )
    (net (code "54") (name "Net-(U8-~{WDO})") (class "Default")
      (node (ref "R32") (pin "1") (pinfunction "1_1") (pintype "passive"))
      (node (ref "U8") (pin "7") (pinfunction "~{WDO}_7") (pintype "output"))
    )
    (net (code "55") (name "VBUS") (class "Default")
      (node (ref "C5") (pin "2") (pinfunction "2_2") (pintype "passive"))
      (node (ref "C6") (pin "2") (pinfunction "2_2") (pintype "passive"))
      (node (ref "D5") (pin "A") (pinfunction "A_A") (pintype "passive"))
      (node (ref "TP5") (pin "1") (pinfunction "TP_1") (pintype "passive"))
      (node (ref "U1") (pin "17") (pinfunction "RX_17") (pintype "passive"))
      (node (ref "U1") (pin "3") (pinfunction "VBUS_3") (pintype "passive"))
    )
    (net (code "56") (name "unconnected-(U1-C4-Pad45)") (class "Default")
      (node (ref "U1") (pin "45") (pinfunction "C4_45") (pintype "passive+no_connect"))
    )
    (net (code "57") (name "unconnected-(U1-C5-Pad44)") (class "Default")
      (node (ref "U1") (pin "44") (pinfunction "C5_44") (pintype "passive+no_connect"))
    )
    (net (code "58") (name "unconnected-(U1-DAC-Pad20)") (class "Default")
      (node (ref "U1") (pin "20") (pinfunction "DAC_20") (pintype "passive+no_connect"))
    )
    (net (code "59") (name "unconnected-(U1-NC-Pad6)") (class "Default")
      (node (ref "U1") (pin "6") (pinfunction "NC_6") (pintype "passive+no_connect"))
    )
    (net (code "60") (name "unconnected-(U1-NC-Pad50)") (class "Default")
      (node (ref "U1") (pin "50") (pinfunction "NC_50") (pintype "passive+no_connect"))
    )
    (net (code "61") (name "unconnected-(U1-PMID-Pad8)") (class "Default")
      (node (ref "U1") (pin "8") (pinfunction "PMID_8") (pintype "passive+no_connect"))
    )
    (net (code "62") (name "unconnected-(U2-NC-Pad4)") (class "Default")
      (node (ref "U2") (pin "4") (pinfunction "NC_4") (pintype "passive+no_connect"))
    )
    (net (code "63") (name "unconnected-(U7-NC-Pad1)") (class "Default")
      (node (ref "U7") (pin "1") (pinfunction "NC_1") (pintype "passive+no_connect"))
    )
    (net (code "64") (name "unconnected-(U7-NC-Pad3)") (class "Default")
      (node (ref "U7") (pin "3") (pinfunction "NC_3") (pintype "passive+no_connect"))
    )
    (net (code "65") (name "unconnected-(U7-NC-Pad6)") (class "Default")
      (node (ref "U7") (pin "6") (pinfunction "NC_6") (pintype "passive+no_connect"))
    )
    (net (code "66") (name "unconnected-(U8-NC-Pad3)") (class "Default")
      (node (ref "U8") (pin "3") (pinfunction "NC_3") (pintype "passive+no_connect"))
    )
    (net (code "67") (name "unconnected-(U11-RESET#{slash}SIO3-Pad7)") (class "Default")
      (node (ref "U11") (pin "7") (pinfunction "RESET#/SIO3_7") (pintype "passive+no_connect"))
    )
    (net (code "68") (name "unconnected-(U11-WP#{slash}SIO2-Pad3)") (class "Default")
      (node (ref "U11") (pin "3") (pinfunction "WP#/SIO2_3") (pintype "passive+no_connect"))
    )
  )
)
